# dual_uart.net
KiCad netlist of a schematic drawn in EAGLE
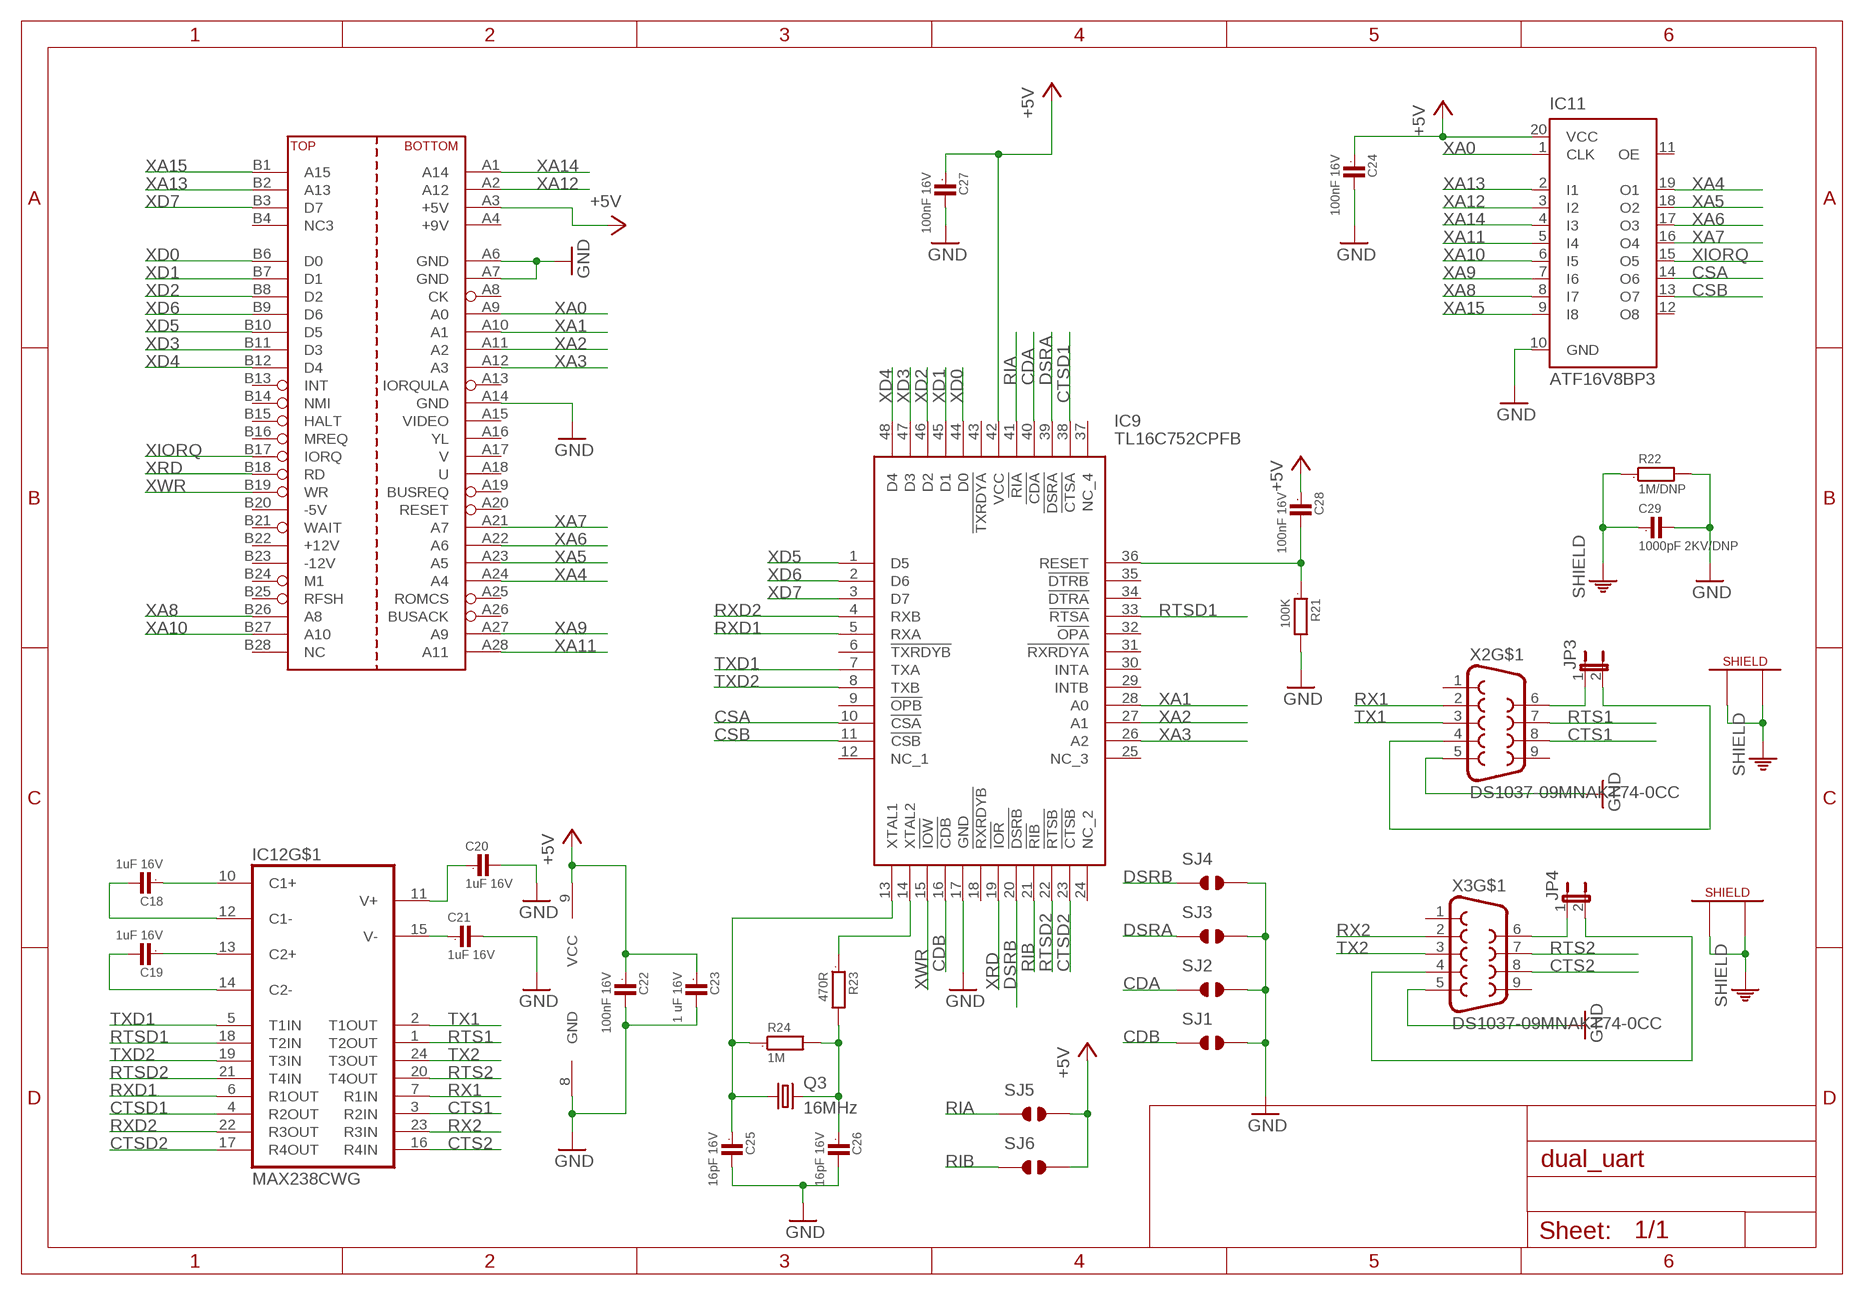
[diagram p0: schematic, sheet 1]

(export (version "E")
  (design (tool "Eeschema 10.0.6"))
  (components
    (comp (ref "C18")
      (value "1uF 16V")
      (footprint "eagle-import:0603")
      (libsource (lib "eagle-import") (part "C0603"))
    )
    (comp (ref "C19")
      (value "1uF 16V")
      (footprint "eagle-import:0603")
      (libsource (lib "eagle-import") (part "C0603"))
    )
    (comp (ref "C20")
      (value "1uF 16V")
      (footprint "eagle-import:0603")
      (libsource (lib "eagle-import") (part "C0603"))
    )
    (comp (ref "C21")
      (value "1uF 16V")
      (footprint "eagle-import:0603")
      (libsource (lib "eagle-import") (part "C0603"))
    )
    (comp (ref "C22")
      (value "100nF 16V")
      (footprint "eagle-import:0603")
      (libsource (lib "eagle-import") (part "C0603"))
    )
    (comp (ref "C23")
      (value "1 uF 16V")
      (footprint "eagle-import:0603")
      (libsource (lib "eagle-import") (part "C0603"))
    )
    (comp (ref "C24")
      (value "100nF 16V")
      (footprint "eagle-import:0603")
      (libsource (lib "eagle-import") (part "C0603"))
    )
    (comp (ref "C25")
      (value "16pF 16V")
      (footprint "eagle-import:0603")
      (libsource (lib "eagle-import") (part "C0603"))
    )
    (comp (ref "C26")
      (value "16pF 16V")
      (footprint "eagle-import:0603")
      (libsource (lib "eagle-import") (part "C0603"))
    )
    (comp (ref "C27")
      (value "100nF 16V")
      (footprint "eagle-import:0603")
      (libsource (lib "eagle-import") (part "C0603"))
    )
    (comp (ref "C28")
      (value "100nF 16V")
      (footprint "eagle-import:0603")
      (libsource (lib "eagle-import") (part "C0603"))
    )
    (comp (ref "C29")
      (value "1000pF 2KV/DNP")
      (footprint "eagle-import:1210")
      (libsource (lib "eagle-import") (part "C1210"))
    )
    (comp (ref "CONN2")
      (value "ZX_EDGE_DAUGHTERBOARD")
      (footprint "eagle-import:ZX-EDGE-DAUGHTERBOARD@1")
      (libsource (lib "eagle-import") (part "ZX_EDGE_DAUGHTERBOARD"))
    )
    (comp (ref "IC9")
      (value "TL16C752CPFB")
      (footprint "eagle-import:QFP50P900X900X120-48N")
      (fields (field (name "MOUSER_PART_NUMBER") "595-TL16C752CPFB"))
      (libsource (lib "eagle-import") (part "TL16C752CPFB"))
    )
    (comp (ref "IC11")
      (value "ATF16V8BP3")
      (footprint "eagle-import:DIL20")
      (fields (field (name "MPN") "ATF16V8CZ-15PU"))
      (libsource (lib "eagle-import") (part "ATF16V8BP3"))
    )
    (comp (ref "IC12")
      (value "MAX238CWG")
      (footprint "eagle-import:SO24L")
      (libsource (lib "eagle-import") (part "MAX238WGC"))
    )
    (comp (ref "JP3")
      (value "JP1E")
      (footprint "eagle-import:JP1")
      (libsource (lib "eagle-import") (part "JP1E"))
    )
    (comp (ref "JP4")
      (value "JP1E")
      (footprint "eagle-import:JP1")
      (libsource (lib "eagle-import") (part "JP1E"))
    )
    (comp (ref "Q3")
      (value "16MHz")
      (footprint "eagle-import:HC49_S")
      (libsource (lib "eagle-import") (part "CRYSTALHC49S"))
    )
    (comp (ref "R21")
      (value "100K")
      (footprint "eagle-import:0603")
      (libsource (lib "eagle-import") (part "R0603"))
    )
    (comp (ref "R22")
      (value "1M/DNP")
      (footprint "eagle-import:0805")
      (libsource (lib "eagle-import") (part "R0805"))
    )
    (comp (ref "R23")
      (value "470R")
      (footprint "eagle-import:0603")
      (libsource (lib "eagle-import") (part "R0603"))
    )
    (comp (ref "R24")
      (value "1M")
      (footprint "eagle-import:0603")
      (libsource (lib "eagle-import") (part "R0603"))
    )
    (comp (ref "SJ1")
      (value "JUMPER_SOLDER_1X2")
      (footprint "eagle-import:JUMPER_SOLDER_1X2")
      (libsource (lib "eagle-import") (part "JUMPER_SOLDER_1X2"))
    )
    (comp (ref "SJ2")
      (value "JUMPER_SOLDER_1X2")
      (footprint "eagle-import:JUMPER_SOLDER_1X2")
      (libsource (lib "eagle-import") (part "JUMPER_SOLDER_1X2"))
    )
    (comp (ref "SJ3")
      (value "JUMPER_SOLDER_1X2")
      (footprint "eagle-import:JUMPER_SOLDER_1X2")
      (libsource (lib "eagle-import") (part "JUMPER_SOLDER_1X2"))
    )
    (comp (ref "SJ4")
      (value "JUMPER_SOLDER_1X2")
      (footprint "eagle-import:JUMPER_SOLDER_1X2")
      (libsource (lib "eagle-import") (part "JUMPER_SOLDER_1X2"))
    )
    (comp (ref "SJ5")
      (value "JUMPER_SOLDER_1X2")
      (footprint "eagle-import:JUMPER_SOLDER_1X2")
      (libsource (lib "eagle-import") (part "JUMPER_SOLDER_1X2"))
    )
    (comp (ref "SJ6")
      (value "JUMPER_SOLDER_1X2")
      (footprint "eagle-import:JUMPER_SOLDER_1X2")
      (libsource (lib "eagle-import") (part "JUMPER_SOLDER_1X2"))
    )
    (comp (ref "X2")
      (value "DS1037-09MNAKT74-0CC")
      (footprint "eagle-import:DB9_MALE")
      (libsource (lib "eagle-import") (part "DB9MALE"))
    )
    (comp (ref "X3")
      (value "DS1037-09MNAKT74-0CC")
      (footprint "eagle-import:DB9_MALE")
      (libsource (lib "eagle-import") (part "DB9MALE"))
    )
  )
  (nets
    (net (code "1") (name "+5V") (class "Default")
      (node (ref "C22") (pin "1") (pinfunction "1_1") (pintype "passive"))
      (node (ref "C23") (pin "1") (pinfunction "1_1") (pintype "passive"))
      (node (ref "C24") (pin "1") (pinfunction "1_1") (pintype "passive"))
      (node (ref "C27") (pin "1") (pinfunction "1_1") (pintype "passive"))
      (node (ref "C28") (pin "1") (pinfunction "1_1") (pintype "passive"))
      (node (ref "CONN2") (pin "A3") (pinfunction "+5V_A3") (pintype "power_in"))
      (node (ref "IC11") (pin "20") (pinfunction "VCC_20") (pintype "power_in"))
      (node (ref "IC12") (pin "9") (pinfunction "VCC_9") (pintype "power_in"))
      (node (ref "IC9") (pin "42") (pinfunction "VCC_42") (pintype "bidirectional"))
      (node (ref "SJ5") (pin "2") (pinfunction "2_2") (pintype "passive"))
      (node (ref "SJ6") (pin "2") (pinfunction "2_2") (pintype "passive"))
    )
    (net (code "2") (name "/+9V") (class "Default")
      (node (ref "CONN2") (pin "A4") (pinfunction "+9V_A4") (pintype "power_in"))
    )
    (net (code "3") (name "/+12V") (class "Default")
      (node (ref "CONN2") (pin "B22") (pinfunction "+12V_B22") (pintype "power_in"))
    )
    (net (code "4") (name "/-5V") (class "Default")
      (node (ref "CONN2") (pin "B20") (pinfunction "-5V_B20") (pintype "power_in"))
    )
    (net (code "5") (name "/-12V") (class "Default")
      (node (ref "CONN2") (pin "B23") (pinfunction "-12V_B23") (pintype "power_in"))
    )
    (net (code "6") (name "/CDA") (class "Default")
      (node (ref "IC9") (pin "40") (pinfunction "~{CDA}_40") (pintype "bidirectional"))
      (node (ref "SJ2") (pin "1") (pinfunction "1_1") (pintype "passive"))
    )
    (net (code "7") (name "/CDB") (class "Default")
      (node (ref "IC9") (pin "16") (pinfunction "~{CDB}_16") (pintype "bidirectional"))
      (node (ref "SJ1") (pin "1") (pinfunction "1_1") (pintype "passive"))
    )
    (net (code "8") (name "/CSA") (class "Default")
      (node (ref "IC11") (pin "14") (pinfunction "O6_14") (pintype "output"))
      (node (ref "IC9") (pin "10") (pinfunction "~{CSA}_10") (pintype "bidirectional"))
    )
    (net (code "9") (name "/CSB") (class "Default")
      (node (ref "IC11") (pin "13") (pinfunction "O7_13") (pintype "output"))
      (node (ref "IC9") (pin "11") (pinfunction "~{CSB}_11") (pintype "bidirectional"))
    )
    (net (code "10") (name "/CTS1") (class "Default")
      (node (ref "IC12") (pin "3") (pinfunction "R2IN_3") (pintype "input"))
      (node (ref "X2") (pin "8") (pinfunction "8_8") (pintype "passive"))
    )
    (net (code "11") (name "/CTS2") (class "Default")
      (node (ref "IC12") (pin "16") (pinfunction "R4IN_16") (pintype "input"))
      (node (ref "X3") (pin "8") (pinfunction "8_8") (pintype "passive"))
    )
    (net (code "12") (name "/CTSD1") (class "Default")
      (node (ref "IC12") (pin "4") (pinfunction "R2OUT_4") (pintype "output"))
      (node (ref "IC9") (pin "38") (pinfunction "~{CTSA}_38") (pintype "bidirectional"))
    )
    (net (code "13") (name "/CTSD2") (class "Default")
      (node (ref "IC12") (pin "17") (pinfunction "R4OUT_17") (pintype "output"))
      (node (ref "IC9") (pin "23") (pinfunction "~{CTSB}_23") (pintype "bidirectional"))
    )
    (net (code "14") (name "/DSRA") (class "Default")
      (node (ref "IC9") (pin "39") (pinfunction "~{DSRA}_39") (pintype "bidirectional"))
      (node (ref "SJ3") (pin "1") (pinfunction "1_1") (pintype "passive"))
    )
    (net (code "15") (name "/DSRB") (class "Default")
      (node (ref "IC9") (pin "20") (pinfunction "~{DSRB}_20") (pintype "bidirectional"))
      (node (ref "SJ4") (pin "1") (pinfunction "1_1") (pintype "passive"))
    )
    (net (code "16") (name "/RIA") (class "Default")
      (node (ref "IC9") (pin "41") (pinfunction "~{RIA}_41") (pintype "bidirectional"))
      (node (ref "SJ5") (pin "1") (pinfunction "1_1") (pintype "passive"))
    )
    (net (code "17") (name "/RIB") (class "Default")
      (node (ref "IC9") (pin "21") (pinfunction "~{RIB}_21") (pintype "bidirectional"))
      (node (ref "SJ6") (pin "1") (pinfunction "1_1") (pintype "passive"))
    )
    (net (code "18") (name "/RTS1") (class "Default")
      (node (ref "IC12") (pin "1") (pinfunction "T2OUT_1") (pintype "output"))
      (node (ref "X2") (pin "7") (pinfunction "7_7") (pintype "passive"))
    )
    (net (code "19") (name "/RTS2") (class "Default")
      (node (ref "IC12") (pin "20") (pinfunction "T4OUT_20") (pintype "output"))
      (node (ref "X3") (pin "7") (pinfunction "7_7") (pintype "passive"))
    )
    (net (code "20") (name "/RTSD1") (class "Default")
      (node (ref "IC12") (pin "18") (pinfunction "T2IN_18") (pintype "input"))
      (node (ref "IC9") (pin "33") (pinfunction "~{RTSA}_33") (pintype "bidirectional"))
    )
    (net (code "21") (name "/RTSD2") (class "Default")
      (node (ref "IC12") (pin "21") (pinfunction "T4IN_21") (pintype "input"))
      (node (ref "IC9") (pin "22") (pinfunction "~{RTSB}_22") (pintype "bidirectional"))
    )
    (net (code "22") (name "/RX1") (class "Default")
      (node (ref "IC12") (pin "7") (pinfunction "R1IN_7") (pintype "input"))
      (node (ref "X2") (pin "2") (pinfunction "2_2") (pintype "passive"))
    )
    (net (code "23") (name "/RX2") (class "Default")
      (node (ref "IC12") (pin "23") (pinfunction "R3IN_23") (pintype "input"))
      (node (ref "X3") (pin "2") (pinfunction "2_2") (pintype "passive"))
    )
    (net (code "24") (name "/RXD1") (class "Default")
      (node (ref "IC12") (pin "6") (pinfunction "R1OUT_6") (pintype "output"))
      (node (ref "IC9") (pin "5") (pinfunction "RXA_5") (pintype "bidirectional"))
    )
    (net (code "25") (name "/RXD2") (class "Default")
      (node (ref "IC12") (pin "22") (pinfunction "R3OUT_22") (pintype "output"))
      (node (ref "IC9") (pin "4") (pinfunction "RXB_4") (pintype "bidirectional"))
    )
    (net (code "26") (name "/TX1") (class "Default")
      (node (ref "IC12") (pin "2") (pinfunction "T1OUT_2") (pintype "output"))
      (node (ref "X2") (pin "3") (pinfunction "3_3") (pintype "passive"))
    )
    (net (code "27") (name "/TX2") (class "Default")
      (node (ref "IC12") (pin "24") (pinfunction "T3OUT_24") (pintype "output"))
      (node (ref "X3") (pin "3") (pinfunction "3_3") (pintype "passive"))
    )
    (net (code "28") (name "/TXD1") (class "Default")
      (node (ref "IC12") (pin "5") (pinfunction "T1IN_5") (pintype "input"))
      (node (ref "IC9") (pin "7") (pinfunction "TXA_7") (pintype "bidirectional"))
    )
    (net (code "29") (name "/TXD2") (class "Default")
      (node (ref "IC12") (pin "19") (pinfunction "T3IN_19") (pintype "input"))
      (node (ref "IC9") (pin "8") (pinfunction "TXB_8") (pintype "bidirectional"))
    )
    (net (code "30") (name "/XA0") (class "Default")
      (node (ref "CONN2") (pin "A9") (pinfunction "A0_A9") (pintype "bidirectional"))
      (node (ref "IC11") (pin "1") (pinfunction "CLK_1") (pintype "input"))
    )
    (net (code "31") (name "/XA1") (class "Default")
      (node (ref "CONN2") (pin "A10") (pinfunction "A1_A10") (pintype "bidirectional"))
      (node (ref "IC9") (pin "28") (pinfunction "A0_28") (pintype "bidirectional"))
    )
    (net (code "32") (name "/XA2") (class "Default")
      (node (ref "CONN2") (pin "A11") (pinfunction "A2_A11") (pintype "bidirectional"))
      (node (ref "IC9") (pin "27") (pinfunction "A1_27") (pintype "bidirectional"))
    )
    (net (code "33") (name "/XA3") (class "Default")
      (node (ref "CONN2") (pin "A12") (pinfunction "A3_A12") (pintype "bidirectional"))
      (node (ref "IC9") (pin "26") (pinfunction "A2_26") (pintype "bidirectional"))
    )
    (net (code "34") (name "/XA4") (class "Default")
      (node (ref "CONN2") (pin "A24") (pinfunction "A4_A24") (pintype "bidirectional"))
      (node (ref "IC11") (pin "19") (pinfunction "O1_19") (pintype "output"))
    )
    (net (code "35") (name "/XA5") (class "Default")
      (node (ref "CONN2") (pin "A23") (pinfunction "A5_A23") (pintype "bidirectional"))
      (node (ref "IC11") (pin "18") (pinfunction "O2_18") (pintype "output"))
    )
    (net (code "36") (name "/XA6") (class "Default")
      (node (ref "CONN2") (pin "A22") (pinfunction "A6_A22") (pintype "bidirectional"))
      (node (ref "IC11") (pin "17") (pinfunction "O3_17") (pintype "output"))
    )
    (net (code "37") (name "/XA7") (class "Default")
      (node (ref "CONN2") (pin "A21") (pinfunction "A7_A21") (pintype "bidirectional"))
      (node (ref "IC11") (pin "16") (pinfunction "O4_16") (pintype "output"))
    )
    (net (code "38") (name "/XA8") (class "Default")
      (node (ref "CONN2") (pin "B26") (pinfunction "A8_B26") (pintype "bidirectional"))
      (node (ref "IC11") (pin "8") (pinfunction "I7_8") (pintype "input"))
    )
    (net (code "39") (name "/XA9") (class "Default")
      (node (ref "CONN2") (pin "A27") (pinfunction "A9_A27") (pintype "bidirectional"))
      (node (ref "IC11") (pin "7") (pinfunction "I6_7") (pintype "input"))
    )
    (net (code "40") (name "/XA10") (class "Default")
      (node (ref "CONN2") (pin "B27") (pinfunction "A10_B27") (pintype "bidirectional"))
      (node (ref "IC11") (pin "6") (pinfunction "I5_6") (pintype "input"))
    )
    (net (code "41") (name "/XA11") (class "Default")
      (node (ref "CONN2") (pin "A28") (pinfunction "A11_A28") (pintype "bidirectional"))
      (node (ref "IC11") (pin "5") (pinfunction "I4_5") (pintype "input"))
    )
    (net (code "42") (name "/XA12") (class "Default")
      (node (ref "CONN2") (pin "A2") (pinfunction "A12_A2") (pintype "bidirectional"))
      (node (ref "IC11") (pin "3") (pinfunction "I2_3") (pintype "input"))
    )
    (net (code "43") (name "/XA13") (class "Default")
      (node (ref "CONN2") (pin "B2") (pinfunction "A13_B2") (pintype "bidirectional"))
      (node (ref "IC11") (pin "2") (pinfunction "I1_2") (pintype "input"))
    )
    (net (code "44") (name "/XA14") (class "Default")
      (node (ref "CONN2") (pin "A1") (pinfunction "A14_A1") (pintype "bidirectional"))
      (node (ref "IC11") (pin "4") (pinfunction "I3_4") (pintype "input"))
    )
    (net (code "45") (name "/XA15") (class "Default")
      (node (ref "CONN2") (pin "B1") (pinfunction "A15_B1") (pintype "bidirectional"))
      (node (ref "IC11") (pin "9") (pinfunction "I8_9") (pintype "input"))
    )
    (net (code "46") (name "/XD0") (class "Default")
      (node (ref "CONN2") (pin "B6") (pinfunction "D0_B6") (pintype "bidirectional"))
      (node (ref "IC9") (pin "44") (pinfunction "D0_44") (pintype "bidirectional"))
    )
    (net (code "47") (name "/XD1") (class "Default")
      (node (ref "CONN2") (pin "B7") (pinfunction "D1_B7") (pintype "bidirectional"))
      (node (ref "IC9") (pin "45") (pinfunction "D1_45") (pintype "bidirectional"))
    )
    (net (code "48") (name "/XD2") (class "Default")
      (node (ref "CONN2") (pin "B8") (pinfunction "D2_B8") (pintype "bidirectional"))
      (node (ref "IC9") (pin "46") (pinfunction "D2_46") (pintype "bidirectional"))
    )
    (net (code "49") (name "/XD3") (class "Default")
      (node (ref "CONN2") (pin "B11") (pinfunction "D3_B11") (pintype "bidirectional"))
      (node (ref "IC9") (pin "47") (pinfunction "D3_47") (pintype "bidirectional"))
    )
    (net (code "50") (name "/XD4") (class "Default")
      (node (ref "CONN2") (pin "B12") (pinfunction "D4_B12") (pintype "bidirectional"))
      (node (ref "IC9") (pin "48") (pinfunction "D4_48") (pintype "bidirectional"))
    )
    (net (code "51") (name "/XD5") (class "Default")
      (node (ref "CONN2") (pin "B10") (pinfunction "D5_B10") (pintype "bidirectional"))
      (node (ref "IC9") (pin "1") (pinfunction "D5_1") (pintype "bidirectional"))
    )
    (net (code "52") (name "/XD6") (class "Default")
      (node (ref "CONN2") (pin "B9") (pinfunction "D6_B9") (pintype "bidirectional"))
      (node (ref "IC9") (pin "2") (pinfunction "D6_2") (pintype "bidirectional"))
    )
    (net (code "53") (name "/XD7") (class "Default")
      (node (ref "CONN2") (pin "B3") (pinfunction "D7_B3") (pintype "bidirectional"))
      (node (ref "IC9") (pin "3") (pinfunction "D7_3") (pintype "bidirectional"))
    )
    (net (code "54") (name "/XIORQ") (class "Default")
      (node (ref "CONN2") (pin "B17") (pinfunction "IORQ_B17") (pintype "bidirectional"))
      (node (ref "IC11") (pin "15") (pinfunction "O5_15") (pintype "output"))
    )
    (net (code "55") (name "/XRD") (class "Default")
      (node (ref "CONN2") (pin "B18") (pinfunction "RD_B18") (pintype "bidirectional"))
      (node (ref "IC9") (pin "19") (pinfunction "~{IOR}_19") (pintype "bidirectional"))
    )
    (net (code "56") (name "/XWR") (class "Default")
      (node (ref "CONN2") (pin "B19") (pinfunction "WR_B19") (pintype "bidirectional"))
      (node (ref "IC9") (pin "15") (pinfunction "~{IOW}_15") (pintype "bidirectional"))
    )
    (net (code "57") (name "GND") (class "Default")
      (node (ref "C20") (pin "2") (pinfunction "2_2") (pintype "passive"))
      (node (ref "C21") (pin "2") (pinfunction "2_2") (pintype "passive"))
      (node (ref "C22") (pin "2") (pinfunction "2_2") (pintype "passive"))
      (node (ref "C23") (pin "2") (pinfunction "2_2") (pintype "passive"))
      (node (ref "C24") (pin "2") (pinfunction "2_2") (pintype "passive"))
      (node (ref "C25") (pin "2") (pinfunction "2_2") (pintype "passive"))
      (node (ref "C26") (pin "2") (pinfunction "2_2") (pintype "passive"))
      (node (ref "C27") (pin "2") (pinfunction "2_2") (pintype "passive"))
      (node (ref "C29") (pin "2") (pinfunction "2_2") (pintype "passive"))
      (node (ref "CONN2") (pin "A14") (pinfunction "GND_A14") (pintype "power_in"))
      (node (ref "CONN2") (pin "A6") (pinfunction "GND_A6") (pintype "power_in"))
      (node (ref "CONN2") (pin "A7") (pinfunction "GND_A7") (pintype "power_in"))
      (node (ref "IC11") (pin "10") (pinfunction "GND_10") (pintype "power_in"))
      (node (ref "IC12") (pin "8") (pinfunction "GND_8") (pintype "power_in"))
      (node (ref "IC9") (pin "17") (pinfunction "GND_17") (pintype "bidirectional"))
      (node (ref "R21") (pin "2") (pinfunction "2_2") (pintype "passive"))
      (node (ref "R22") (pin "2") (pinfunction "2_2") (pintype "passive"))
      (node (ref "SJ1") (pin "2") (pinfunction "2_2") (pintype "passive"))
      (node (ref "SJ2") (pin "2") (pinfunction "2_2") (pintype "passive"))
      (node (ref "SJ3") (pin "2") (pinfunction "2_2") (pintype "passive"))
      (node (ref "SJ4") (pin "2") (pinfunction "2_2") (pintype "passive"))
      (node (ref "X2") (pin "5") (pinfunction "5_5") (pintype "passive"))
      (node (ref "X3") (pin "5") (pinfunction "5_5") (pintype "passive"))
    )
    (net (code "58") (name "Net-(C26-Pad1)") (class "Default")
      (node (ref "C26") (pin "1") (pinfunction "1_1") (pintype "passive"))
      (node (ref "Q3") (pin "2") (pinfunction "2_2") (pintype "passive"))
      (node (ref "R23") (pin "2") (pinfunction "2_2") (pintype "passive"))
      (node (ref "R24") (pin "2") (pinfunction "2_2") (pintype "passive"))
    )
    (net (code "59") (name "Net-(IC9-RESET)") (class "Default")
      (node (ref "C28") (pin "2") (pinfunction "2_2") (pintype "passive"))
      (node (ref "IC9") (pin "36") (pinfunction "RESET_36") (pintype "bidirectional"))
      (node (ref "R21") (pin "1") (pinfunction "1_1") (pintype "passive"))
    )
    (net (code "60") (name "Net-(IC9-XTAL1)") (class "Default")
      (node (ref "C25") (pin "1") (pinfunction "1_1") (pintype "passive"))
      (node (ref "IC9") (pin "13") (pinfunction "XTAL1_13") (pintype "bidirectional"))
      (node (ref "Q3") (pin "1") (pinfunction "1_1") (pintype "passive"))
      (node (ref "R24") (pin "1") (pinfunction "1_1") (pintype "passive"))
    )
    (net (code "61") (name "Net-(IC9-XTAL2)") (class "Default")
      (node (ref "IC9") (pin "14") (pinfunction "XTAL2_14") (pintype "bidirectional"))
      (node (ref "R23") (pin "1") (pinfunction "1_1") (pintype "passive"))
    )
    (net (code "62") (name "Net-(IC12A-C1+)") (class "Default")
      (node (ref "C18") (pin "1") (pinfunction "1_1") (pintype "passive"))
      (node (ref "IC12") (pin "10") (pinfunction "C1+_10") (pintype "bidirectional"))
    )
    (net (code "63") (name "Net-(IC12A-C1-)") (class "Default")
      (node (ref "C18") (pin "2") (pinfunction "2_2") (pintype "passive"))
      (node (ref "IC12") (pin "12") (pinfunction "C1-_12") (pintype "bidirectional"))
    )
    (net (code "64") (name "Net-(IC12A-C2+)") (class "Default")
      (node (ref "C19") (pin "1") (pinfunction "1_1") (pintype "passive"))
      (node (ref "IC12") (pin "13") (pinfunction "C2+_13") (pintype "bidirectional"))
    )
    (net (code "65") (name "Net-(IC12A-C2-)") (class "Default")
      (node (ref "C19") (pin "2") (pinfunction "2_2") (pintype "passive"))
      (node (ref "IC12") (pin "14") (pinfunction "C2-_14") (pintype "bidirectional"))
    )
    (net (code "66") (name "Net-(IC12A-V+)") (class "Default")
      (node (ref "C20") (pin "1") (pinfunction "1_1") (pintype "passive"))
      (node (ref "IC12") (pin "11") (pinfunction "V+_11") (pintype "bidirectional"))
    )
    (net (code "67") (name "Net-(IC12A-V-)") (class "Default")
      (node (ref "C21") (pin "1") (pinfunction "1_1") (pintype "passive"))
      (node (ref "IC12") (pin "15") (pinfunction "V-_15") (pintype "bidirectional"))
    )
    (net (code "68") (name "Net-(JP3-Pad1)") (class "Default")
      (node (ref "JP3") (pin "1") (pinfunction "1_1") (pintype "passive"))
      (node (ref "X2") (pin "6") (pinfunction "6_6") (pintype "passive"))
    )
    (net (code "69") (name "Net-(JP3-Pad2)") (class "Default")
      (node (ref "JP3") (pin "2") (pinfunction "2_2") (pintype "passive"))
      (node (ref "X2") (pin "4") (pinfunction "4_4") (pintype "passive"))
    )
    (net (code "70") (name "Net-(JP4-Pad1)") (class "Default")
      (node (ref "JP4") (pin "1") (pinfunction "1_1") (pintype "passive"))
      (node (ref "X3") (pin "6") (pinfunction "6_6") (pintype "passive"))
    )
    (net (code "71") (name "Net-(JP4-Pad2)") (class "Default")
      (node (ref "JP4") (pin "2") (pinfunction "2_2") (pintype "passive"))
      (node (ref "X3") (pin "4") (pinfunction "4_4") (pintype "passive"))
    )
    (net (code "72") (name "SHIELD") (class "Default")
      (node (ref "C29") (pin "1") (pinfunction "1_1") (pintype "passive"))
      (node (ref "R22") (pin "1") (pinfunction "1_1") (pintype "passive"))
      (node (ref "X2") (pin "G1") (pinfunction "P$1_G1") (pintype "passive"))
      (node (ref "X2") (pin "G2") (pinfunction "P$2_G2") (pintype "passive"))
      (node (ref "X3") (pin "G1") (pinfunction "P$1_G1") (pintype "passive"))
      (node (ref "X3") (pin "G2") (pinfunction "P$2_G2") (pintype "passive"))
    )
    (net (code "73") (name "unconnected-(CONN2-BUSACK-PadA26)") (class "Default")
      (node (ref "CONN2") (pin "A26") (pinfunction "BUSACK_A26") (pintype "bidirectional"))
    )
    (net (code "74") (name "unconnected-(CONN2-BUSREQ-PadA19)") (class "Default")
      (node (ref "CONN2") (pin "A19") (pinfunction "BUSREQ_A19") (pintype "bidirectional"))
    )
    (net (code "75") (name "unconnected-(CONN2-CK-PadA8)") (class "Default")
      (node (ref "CONN2") (pin "A8") (pinfunction "CK_A8") (pintype "bidirectional"))
    )
    (net (code "76") (name "unconnected-(CONN2-HALT-PadB15)") (class "Default")
      (node (ref "CONN2") (pin "B15") (pinfunction "HALT_B15") (pintype "bidirectional"))
    )
    (net (code "77") (name "unconnected-(CONN2-INT-PadB13)") (class "Default")
      (node (ref "CONN2") (pin "B13") (pinfunction "INT_B13") (pintype "bidirectional"))
    )
    (net (code "78") (name "unconnected-(CONN2-IORQULA-PadA13)") (class "Default")
      (node (ref "CONN2") (pin "A13") (pinfunction "IORQULA_A13") (pintype "bidirectional"))
    )
    (net (code "79") (name "unconnected-(CONN2-M1-PadB24)") (class "Default")
      (node (ref "CONN2") (pin "B24") (pinfunction "M1_B24") (pintype "bidirectional"))
    )
    (net (code "80") (name "unconnected-(CONN2-MREQ-PadB16)") (class "Default")
      (node (ref "CONN2") (pin "B16") (pinfunction "MREQ_B16") (pintype "bidirectional"))
    )
    (net (code "81") (name "unconnected-(CONN2-NC-PadB28)") (class "Default")
      (node (ref "CONN2") (pin "B28") (pinfunction "NC_B28") (pintype "bidirectional"))
    )
    (net (code "82") (name "unconnected-(CONN2-NC3-PadB4)") (class "Default")
      (node (ref "CONN2") (pin "B4") (pinfunction "NC3_B4") (pintype "passive"))
    )
    (net (code "83") (name "unconnected-(CONN2-NMI-PadB14)") (class "Default")
      (node (ref "CONN2") (pin "B14") (pinfunction "NMI_B14") (pintype "bidirectional"))
    )
    (net (code "84") (name "unconnected-(CONN2-RESET-PadA20)") (class "Default")
      (node (ref "CONN2") (pin "A20") (pinfunction "RESET_A20") (pintype "bidirectional"))
    )
    (net (code "85") (name "unconnected-(CONN2-RFSH-PadB25)") (class "Default")
      (node (ref "CONN2") (pin "B25") (pinfunction "RFSH_B25") (pintype "bidirectional"))
    )
    (net (code "86") (name "unconnected-(CONN2-ROMCS-PadA25)") (class "Default")
      (node (ref "CONN2") (pin "A25") (pinfunction "ROMCS_A25") (pintype "bidirectional"))
    )
    (net (code "87") (name "unconnected-(CONN2-U-PadA18)") (class "Default")
      (node (ref "CONN2") (pin "A18") (pinfunction "U_A18") (pintype "bidirectional"))
    )
    (net (code "88") (name "unconnected-(CONN2-V-PadA17)") (class "Default")
      (node (ref "CONN2") (pin "A17") (pinfunction "V_A17") (pintype "bidirectional"))
    )
    (net (code "89") (name "unconnected-(CONN2-VIDEO-PadA15)") (class "Default")
      (node (ref "CONN2") (pin "A15") (pinfunction "VIDEO_A15") (pintype "bidirectional"))
    )
    (net (code "90") (name "unconnected-(CONN2-WAIT-PadB21)") (class "Default")
      (node (ref "CONN2") (pin "B21") (pinfunction "WAIT_B21") (pintype "bidirectional"))
    )
    (net (code "91") (name "unconnected-(CONN2-YL-PadA16)") (class "Default")
      (node (ref "CONN2") (pin "A16") (pinfunction "YL_A16") (pintype "bidirectional"))
    )
    (net (code "92") (name "unconnected-(IC9-INTA-Pad30)") (class "Default")
      (node (ref "IC9") (pin "30") (pinfunction "INTA_30") (pintype "bidirectional"))
    )
    (net (code "93") (name "unconnected-(IC9-INTB-Pad29)") (class "Default")
      (node (ref "IC9") (pin "29") (pinfunction "INTB_29") (pintype "bidirectional"))
    )
    (net (code "94") (name "unconnected-(IC9-NC_1-Pad12)") (class "Default")
      (node (ref "IC9") (pin "12") (pinfunction "NC_1_12") (pintype "bidirectional"))
    )
    (net (code "95") (name "unconnected-(IC9-NC_2-Pad24)") (class "Default")
      (node (ref "IC9") (pin "24") (pinfunction "NC_2_24") (pintype "bidirectional"))
    )
    (net (code "96") (name "unconnected-(IC9-NC_3-Pad25)") (class "Default")
      (node (ref "IC9") (pin "25") (pinfunction "NC_3_25") (pintype "bidirectional"))
    )
    (net (code "97") (name "unconnected-(IC9-NC_4-Pad37)") (class "Default")
      (node (ref "IC9") (pin "37") (pinfunction "NC_4_37") (pintype "bidirectional"))
    )
    (net (code "98") (name "unconnected-(IC9-~{DTRA}-Pad34)") (class "Default")
      (node (ref "IC9") (pin "34") (pinfunction "~{DTRA}_34") (pintype "bidirectional"))
    )
    (net (code "99") (name "unconnected-(IC9-~{DTRB}-Pad35)") (class "Default")
      (node (ref "IC9") (pin "35") (pinfunction "~{DTRB}_35") (pintype "bidirectional"))
    )
    (net (code "100") (name "unconnected-(IC9-~{OPA}-Pad32)") (class "Default")
      (node (ref "IC9") (pin "32") (pinfunction "~{OPA}_32") (pintype "bidirectional"))
    )
    (net (code "101") (name "unconnected-(IC9-~{OPB}-Pad9)") (class "Default")
      (node (ref "IC9") (pin "9") (pinfunction "~{OPB}_9") (pintype "bidirectional"))
    )
    (net (code "102") (name "unconnected-(IC9-~{RXRDYA}-Pad31)") (class "Default")
      (node (ref "IC9") (pin "31") (pinfunction "~{RXRDYA}_31") (pintype "bidirectional"))
    )
    (net (code "103") (name "unconnected-(IC9-~{RXRDYB}-Pad18)") (class "Default")
      (node (ref "IC9") (pin "18") (pinfunction "~{RXRDYB}_18") (pintype "bidirectional"))
    )
    (net (code "104") (name "unconnected-(IC9-~{TXRDYA}-Pad43)") (class "Default")
      (node (ref "IC9") (pin "43") (pinfunction "~{TXRDYA}_43") (pintype "bidirectional"))
    )
    (net (code "105") (name "unconnected-(IC9-~{TXRDYB}-Pad6)") (class "Default")
      (node (ref "IC9") (pin "6") (pinfunction "~{TXRDYB}_6") (pintype "bidirectional"))
    )
    (net (code "106") (name "unconnected-(IC11-O8-Pad12)") (class "Default")
      (node (ref "IC11") (pin "12") (pinfunction "O8_12") (pintype "output"))
    )
    (net (code "107") (name "unconnected-(IC11-OE-Pad11)") (class "Default")
      (node (ref "IC11") (pin "11") (pinfunction "OE_11") (pintype "input"))
    )
    (net (code "108") (name "unconnected-(X2-Pad1)") (class "Default")
      (node (ref "X2") (pin "1") (pinfunction "1_1") (pintype "passive"))
    )
    (net (code "109") (name "unconnected-(X2-Pad9)") (class "Default")
      (node (ref "X2") (pin "9") (pinfunction "9_9") (pintype "passive"))
    )
    (net (code "110") (name "unconnected-(X3-Pad1)") (class "Default")
      (node (ref "X3") (pin "1") (pinfunction "1_1") (pintype "passive"))
    )
    (net (code "111") (name "unconnected-(X3-Pad9)") (class "Default")
      (node (ref "X3") (pin "9") (pinfunction "9_9") (pintype "passive"))
    )
  )
)
